# PMODE.net
KiCad netlist of a schematic drawn in Altium Designer
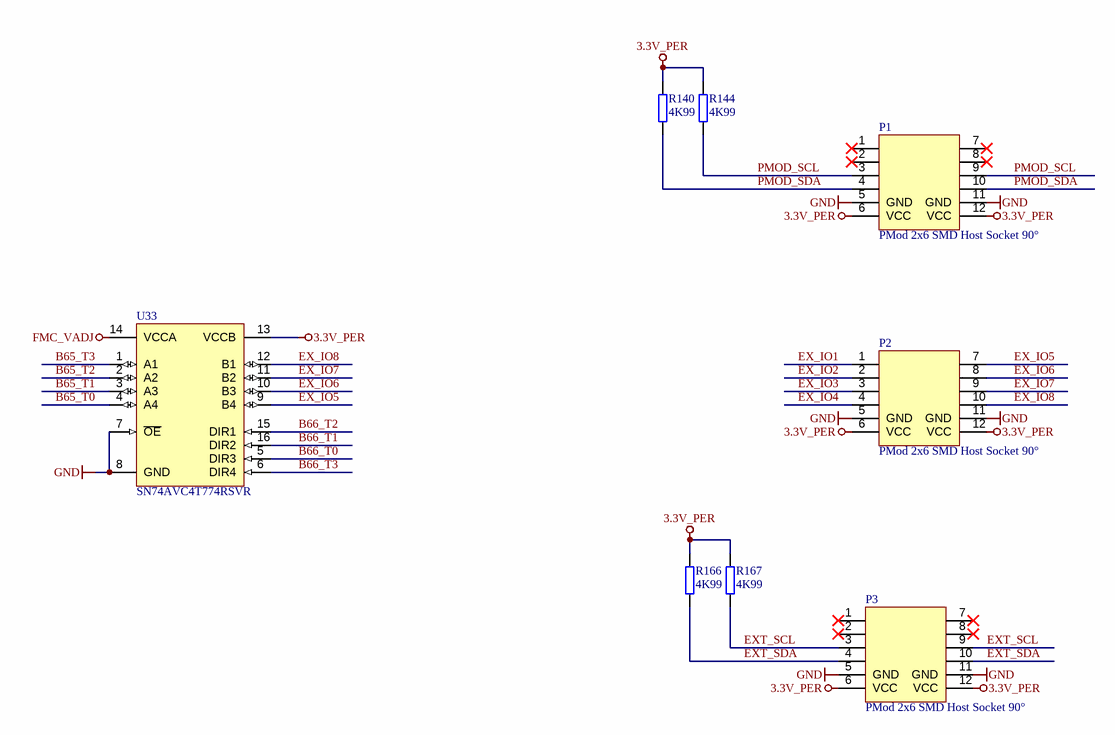
[diagram p0: PMODE.schdoc]

(export (version "E")
  (design (tool "Eeschema 10.0.6"))
  (components
    (comp (ref "P1")
      (value "PMod 2x6 SMD Host Socket 90°")
      (footprint "610112249221")
      (description "PMod 2x6 SMD Socket 90°")
      (libsource (lib "TE") (part "PMod2x6"))
    )
    (comp (ref "P2")
      (value "PMod 2x6 SMD Host Socket 90°")
      (footprint "610112249221")
      (description "PMod 2x6 SMD Socket 90°")
      (libsource (lib "TE") (part "PMod2x6"))
    )
    (comp (ref "P3")
      (value "PMod 2x6 SMD Host Socket 90°")
      (footprint "610112249221")
      (description "PMod 2x6 SMD Socket 90°")
      (libsource (lib "TE") (part "PMod2x6"))
    )
    (comp (ref "R140")
      (value "4K99")
      (footprint "RESC1005X40N")
      (description "WID SMD 4K99 1% 0,063W")
      (fields (field (name "TOLERANCE") "1%"))
      (libsource (lib "TE") (part "RES"))
    )
    (comp (ref "R144")
      (value "4K99")
      (footprint "RESC1005X40N")
      (description "WID SMD 4K99 1% 0,063W")
      (fields (field (name "TOLERANCE") "1%"))
      (libsource (lib "TE") (part "RES"))
    )
    (comp (ref "R166")
      (value "4K99")
      (footprint "RESC1005X40N")
      (description "WID SMD 4K99 1% 0,063W")
      (fields (field (name "TOLERANCE") "1%"))
      (libsource (lib "TE") (part "RES"))
    )
    (comp (ref "R167")
      (value "4K99")
      (footprint "RESC1005X40N")
      (description "WID SMD 4K99 1% 0,063W")
      (fields (field (name "TOLERANCE") "1%"))
      (libsource (lib "TE") (part "RES"))
    )
    (comp (ref "U33")
      (value "SN74AVC4T774RSVR")
      (footprint "QFN40P260X180X55-16N")
      (libsource (lib "TE") (part "SN74AVC4T774RSVR"))
    )
  )
  (nets
    (net (code "1") (name "/B65_T0") (class "Default")
      (node (ref "U33") (pin "4") (pinfunction "A4_4") (pintype "bidirectional"))
    )
    (net (code "2") (name "/B65_T1") (class "Default")
      (node (ref "U33") (pin "3") (pinfunction "A3_3") (pintype "bidirectional"))
    )
    (net (code "3") (name "/B65_T2") (class "Default")
      (node (ref "U33") (pin "2") (pinfunction "A2_2") (pintype "bidirectional"))
    )
    (net (code "4") (name "/B65_T3") (class "Default")
      (node (ref "U33") (pin "1") (pinfunction "A1_1") (pintype "bidirectional"))
    )
    (net (code "5") (name "/B66_T0") (class "Default")
      (node (ref "U33") (pin "5") (pinfunction "DIR3_5") (pintype "input"))
    )
    (net (code "6") (name "/B66_T1") (class "Default")
      (node (ref "U33") (pin "16") (pinfunction "DIR2_16") (pintype "input"))
    )
    (net (code "7") (name "/B66_T2") (class "Default")
      (node (ref "U33") (pin "15") (pinfunction "DIR1_15") (pintype "input"))
    )
    (net (code "8") (name "/B66_T3") (class "Default")
      (node (ref "U33") (pin "6") (pinfunction "DIR4_6") (pintype "input"))
    )
    (net (code "9") (name "/EXT_SCL") (class "Default")
      (node (ref "P3") (pin "3") (pintype "passive"))
      (node (ref "P3") (pin "9") (pintype "passive"))
      (node (ref "R167") (pin "2") (pinfunction "2_2") (pintype "passive"))
    )
    (net (code "10") (name "/EXT_SDA") (class "Default")
      (node (ref "P3") (pin "10") (pintype "passive"))
      (node (ref "P3") (pin "4") (pintype "passive"))
      (node (ref "R166") (pin "2") (pinfunction "2_2") (pintype "passive"))
    )
    (net (code "11") (name "/EX_IO1") (class "Default") (node (ref "P2") (pin "1") (pintype "passive")))
    (net (code "12") (name "/EX_IO2") (class "Default") (node (ref "P2") (pin "2") (pintype "passive")))
    (net (code "13") (name "/EX_IO3") (class "Default") (node (ref "P2") (pin "3") (pintype "passive")))
    (net (code "14") (name "/EX_IO4") (class "Default") (node (ref "P2") (pin "4") (pintype "passive")))
    (net (code "15") (name "/EX_IO5") (class "Default")
      (node (ref "P2") (pin "7") (pintype "passive"))
      (node (ref "U33") (pin "9") (pinfunction "B4_9") (pintype "bidirectional"))
    )
    (net (code "16") (name "/EX_IO6") (class "Default")
      (node (ref "P2") (pin "8") (pintype "passive"))
      (node (ref "U33") (pin "10") (pinfunction "B3_10") (pintype "bidirectional"))
    )
    (net (code "17") (name "/EX_IO7") (class "Default")
      (node (ref "P2") (pin "9") (pintype "passive"))
      (node (ref "U33") (pin "11") (pinfunction "B2_11") (pintype "bidirectional"))
    )
    (net (code "18") (name "/EX_IO8") (class "Default")
      (node (ref "P2") (pin "10") (pintype "passive"))
      (node (ref "U33") (pin "12") (pinfunction "B1_12") (pintype "bidirectional"))
    )
    (net (code "19") (name "/PMOD_SCL") (class "Default")
      (node (ref "P1") (pin "3") (pintype "passive"))
      (node (ref "P1") (pin "9") (pintype "passive"))
      (node (ref "R144") (pin "2") (pinfunction "2_2") (pintype "passive"))
    )
    (net (code "20") (name "/PMOD_SDA") (class "Default")
      (node (ref "P1") (pin "10") (pintype "passive"))
      (node (ref "P1") (pin "4") (pintype "passive"))
      (node (ref "R140") (pin "2") (pinfunction "2_2") (pintype "passive"))
    )
    (net (code "21") (name "3.3V_PER") (class "Default")
      (node (ref "P1") (pin "12") (pinfunction "VCC_12") (pintype "power_in"))
      (node (ref "P1") (pin "6") (pinfunction "VCC_6") (pintype "power_in"))
      (node (ref "P2") (pin "12") (pinfunction "VCC_12") (pintype "power_in"))
      (node (ref "P2") (pin "6") (pinfunction "VCC_6") (pintype "power_in"))
      (node (ref "P3") (pin "12") (pinfunction "VCC_12") (pintype "power_in"))
      (node (ref "P3") (pin "6") (pinfunction "VCC_6") (pintype "power_in"))
      (node (ref "R140") (pin "1") (pinfunction "1_1") (pintype "passive"))
      (node (ref "R144") (pin "1") (pinfunction "1_1") (pintype "passive"))
      (node (ref "R166") (pin "1") (pinfunction "1_1") (pintype "passive"))
      (node (ref "R167") (pin "1") (pinfunction "1_1") (pintype "passive"))
      (node (ref "U33") (pin "13") (pinfunction "VCCB_13") (pintype "power_in"))
    )
    (net (code "22") (name "FMC_VADJ") (class "Default")
      (node (ref "U33") (pin "14") (pinfunction "VCCA_14") (pintype "power_in"))
    )
    (net (code "23") (name "GND") (class "Default")
      (node (ref "P1") (pin "11") (pinfunction "GND_11") (pintype "power_in"))
      (node (ref "P1") (pin "5") (pinfunction "GND_5") (pintype "power_in"))
      (node (ref "P2") (pin "11") (pinfunction "GND_11") (pintype "power_in"))
      (node (ref "P2") (pin "5") (pinfunction "GND_5") (pintype "power_in"))
      (node (ref "P3") (pin "11") (pinfunction "GND_11") (pintype "power_in"))
      (node (ref "P3") (pin "5") (pinfunction "GND_5") (pintype "power_in"))
      (node (ref "U33") (pin "7") (pinfunction "~{OE}_7") (pintype "input"))
      (node (ref "U33") (pin "8") (pinfunction "GND_8") (pintype "power_in"))
    )
    (net (code "24") (name "unconnected-(P1-Pad1)") (class "Default")
      (node (ref "P1") (pin "1") (pintype "passive+no_connect"))
    )
    (net (code "25") (name "unconnected-(P1-Pad2)") (class "Default")
      (node (ref "P1") (pin "2") (pintype "passive+no_connect"))
    )
    (net (code "26") (name "unconnected-(P1-Pad7)") (class "Default")
      (node (ref "P1") (pin "7") (pintype "passive+no_connect"))
    )
    (net (code "27") (name "unconnected-(P1-Pad8)") (class "Default")
      (node (ref "P1") (pin "8") (pintype "passive+no_connect"))
    )
    (net (code "28") (name "unconnected-(P3-Pad1)") (class "Default")
      (node (ref "P3") (pin "1") (pintype "passive+no_connect"))
    )
    (net (code "29") (name "unconnected-(P3-Pad2)") (class "Default")
      (node (ref "P3") (pin "2") (pintype "passive+no_connect"))
    )
    (net (code "30") (name "unconnected-(P3-Pad7)") (class "Default")
      (node (ref "P3") (pin "7") (pintype "passive+no_connect"))
    )
    (net (code "31") (name "unconnected-(P3-Pad8)") (class "Default")
      (node (ref "P3") (pin "8") (pintype "passive+no_connect"))
    )
  )
)
